# interlock_circuit.net
KiCad netlist of a schematic drawn in Altium Designer
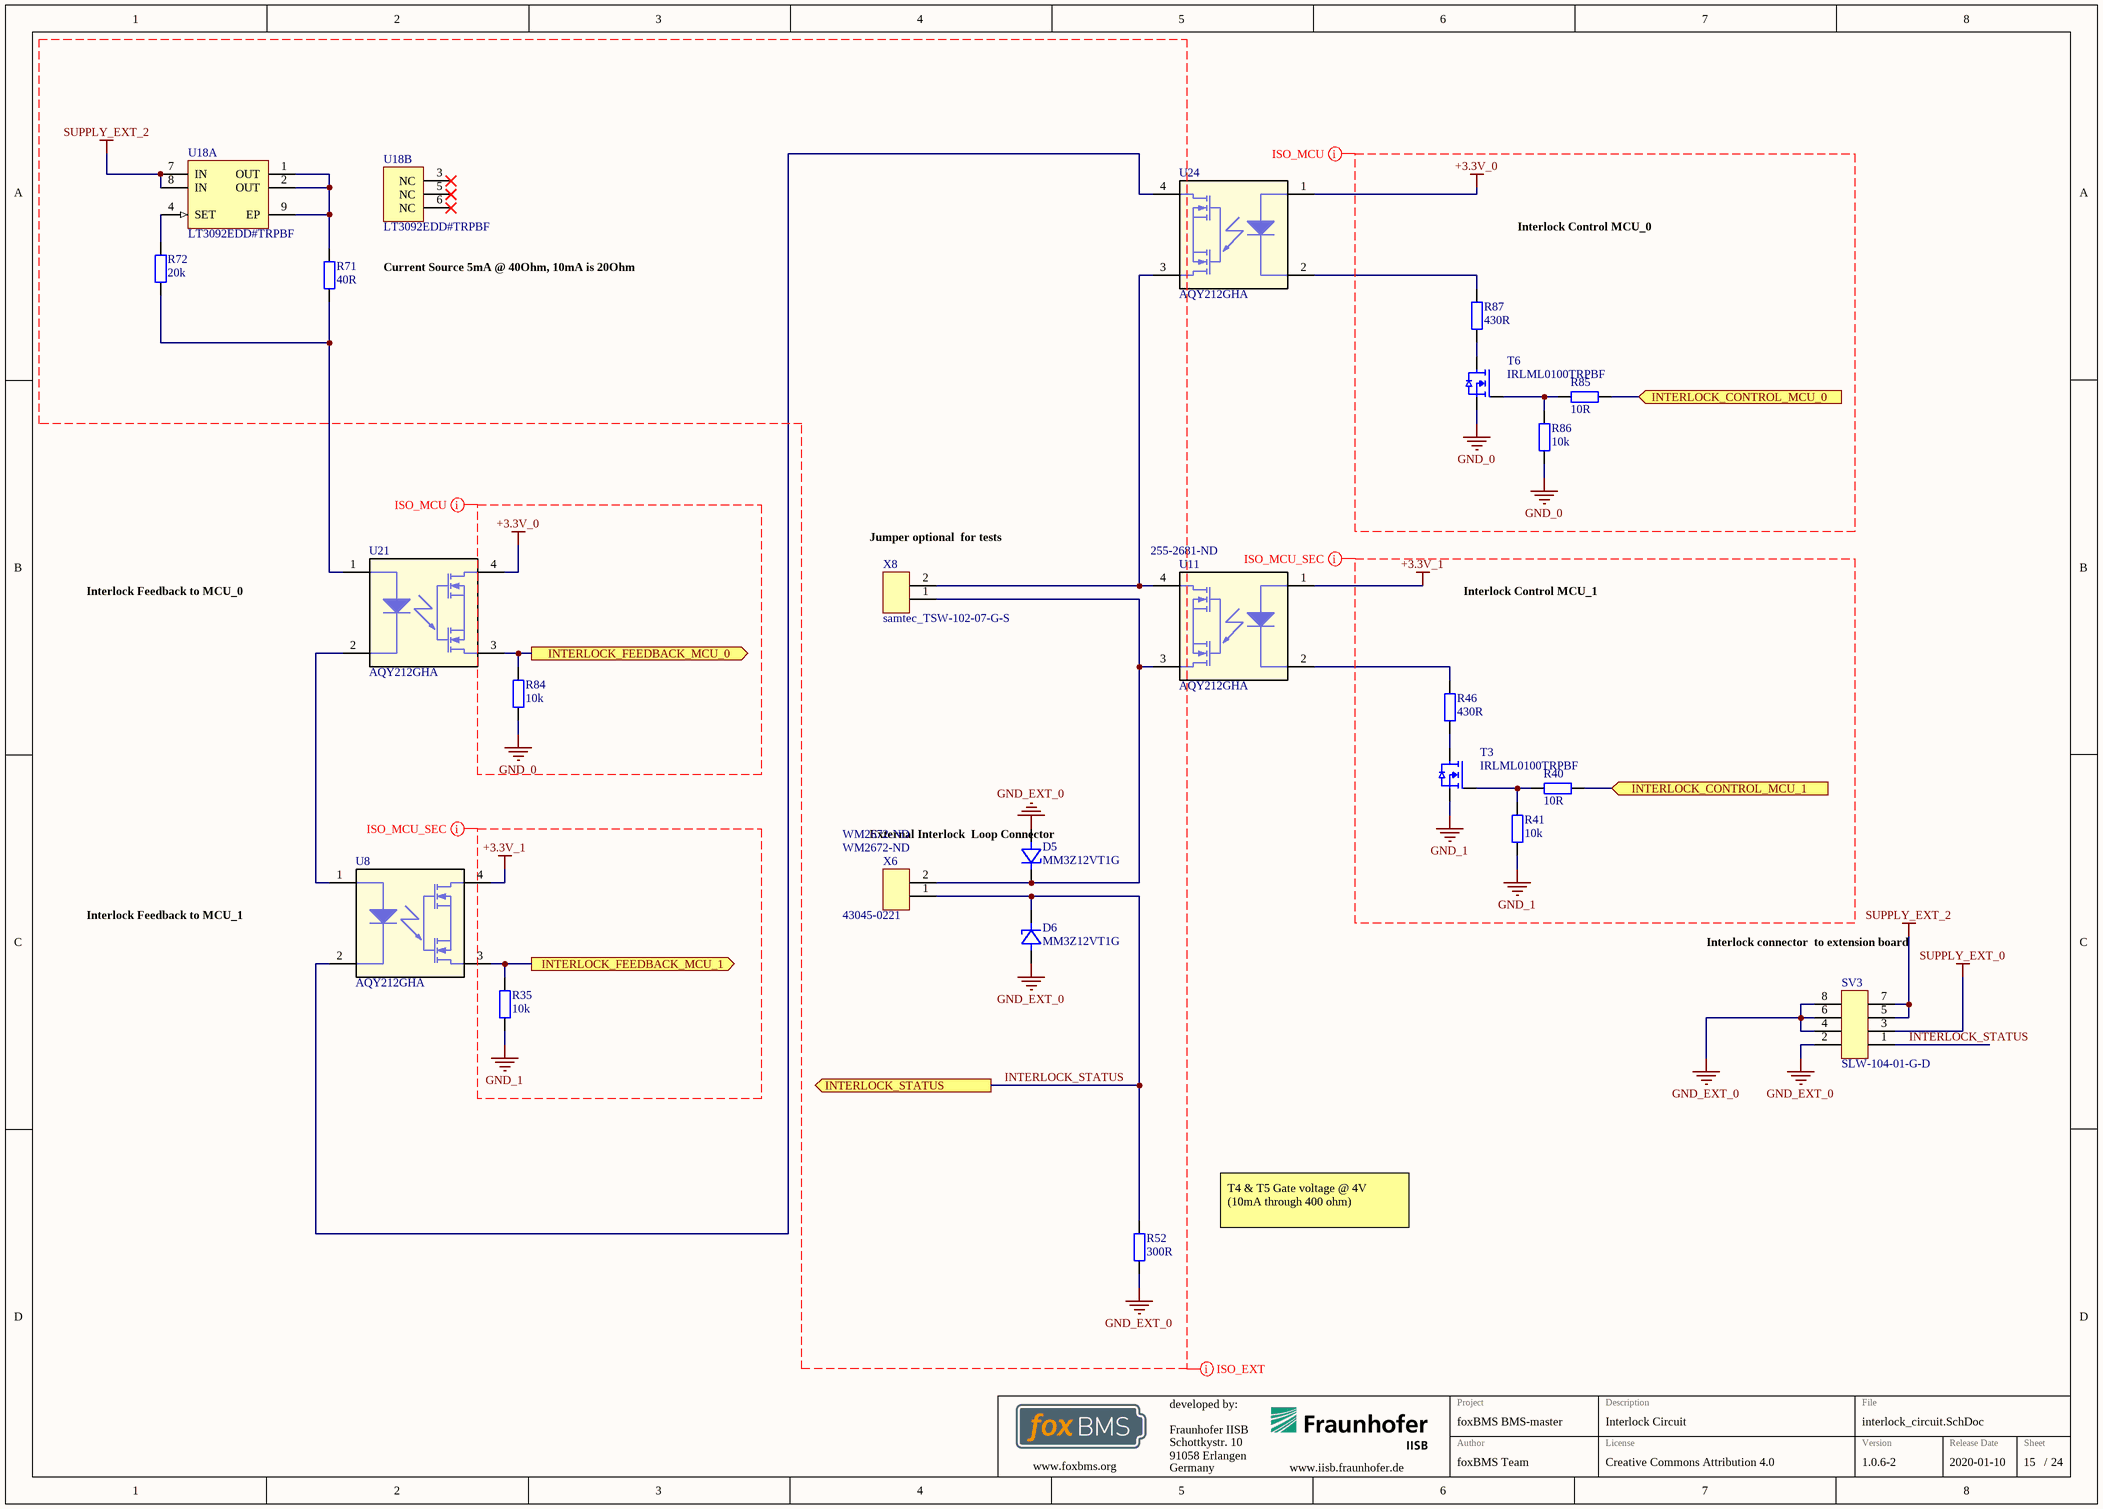
[diagram p0: interlock_circuit.SchDoc]

(export (version "E")
  (design (tool "Eeschema 10.0.6"))
  (components
    (comp (ref "D5")
      (value "MM3Z12VT1G")
      (footprint "SODFL250X110-2N")
      (description "Zener Diode")
      (fields (field (name "MANUFACTURER") "ON Semiconductor"))
      (libsource (lib "OE750") (part "D_Zener"))
    )
    (comp (ref "D6")
      (value "MM3Z12VT1G")
      (footprint "SODFL250X110-2N")
      (description "Zener Diode")
      (fields (field (name "MANUFACTURER") "ON Semiconductor"))
      (libsource (lib "OE750") (part "D_Zener"))
    )
    (comp (ref "R35")
      (value "10k")
      (footprint "0603R")
      (description "SMD Resistor 10k 0603")
      (fields (field (name "PART NUMBER") "gen_R_10k_0603") (field (name "TOLERANCE") "1%"))
      (libsource (lib "master-010106") (part "R"))
    )
    (comp (ref "R40")
      (value "10R")
      (footprint "0603R")
      (description "SMD Resistor 10R 0603")
      (fields (field (name "PART NUMBER") "gen_R_10R_0603") (field (name "TOLERANCE") "1%"))
      (libsource (lib "master-010106") (part "R"))
    )
    (comp (ref "R41")
      (value "10k")
      (footprint "0603R")
      (description "SMD Resistor 10k 0603")
      (fields (field (name "PART NUMBER") "gen_R_10k_0603") (field (name "TOLERANCE") "1%"))
      (libsource (lib "master-010106") (part "R"))
    )
    (comp (ref "R46")
      (value "430R")
      (footprint "0603R")
      (description "SMD Resistor 430R 0603")
      (fields (field (name "PART NUMBER") "gen_R_430R_0603") (field (name "TOLERANCE") "1%"))
      (libsource (lib "master-010106") (part "R"))
    )
    (comp (ref "R52")
      (value "300R")
      (footprint "0805R")
      (description "SMD Resistor 330R 0603")
      (fields (field (name "PART NUMBER") "gen_R_300R_0805") (field (name "POWER") "0.1W"))
      (libsource (lib "master-010106") (part "R"))
    )
    (comp (ref "R71")
      (value "40R")
      (footprint "0805R")
      (description "SMD Resistor 120R 0603")
      (fields (field (name "PART NUMBER") "gen_R_120R_0603") (field (name "TOLERANCE") "1%"))
      (libsource (lib "master-010106") (part "R"))
    )
    (comp (ref "R72")
      (value "20k")
      (footprint "0805R")
      (description "SMD Resistor 120R 0603")
      (fields (field (name "PART NUMBER") "gen_R_120R_0603") (field (name "TOLERANCE") "1%"))
      (libsource (lib "master-010106") (part "R"))
    )
    (comp (ref "R84")
      (value "10k")
      (footprint "0603R")
      (description "SMD Resistor 10k 0603")
      (fields (field (name "PART NUMBER") "gen_R_10k_0603") (field (name "TOLERANCE") "1%"))
      (libsource (lib "master-010106") (part "R"))
    )
    (comp (ref "R85")
      (value "10R")
      (footprint "0603R")
      (description "SMD Resistor 10R 0603")
      (fields (field (name "PART NUMBER") "gen_R_10R_0603") (field (name "TOLERANCE") "1%"))
      (libsource (lib "master-010106") (part "R"))
    )
    (comp (ref "R86")
      (value "10k")
      (footprint "0603R")
      (description "SMD Resistor 10k 0603")
      (fields (field (name "PART NUMBER") "gen_R_10k_0603") (field (name "TOLERANCE") "1%"))
      (libsource (lib "master-010106") (part "R"))
    )
    (comp (ref "R87")
      (value "430R")
      (footprint "0603R")
      (description "SMD Resistor 430R 0603")
      (fields (field (name "PART NUMBER") "gen_R_430R_0603") (field (name "TOLERANCE") "1%"))
      (libsource (lib "master-010106") (part "R"))
    )
    (comp (ref "SV3")
      (value "SLW-104-01-G-D")
      (footprint "SLW_104_01_G_D")
      (description "Board-To-Board Connector, Dual, 2.54 mm, 8 Contacts, Receptacle, SLW Series, Through Hole, 2 Rows")
      (fields (field (name "MANUFACTURER") "Samtec"))
      (libsource (lib "OE750") (part "X2x4"))
    )
    (comp (ref "T3")
      (value "IRLML0100TRPBF")
      (footprint "SOT95P237X110-3N")
      (description "MOSFET-Transistor, n-Kanal, 1.6 A, 100 V, 0.178 ohm, 10 V, 2.5 V")
      (fields (field (name "MANUFACTURER") "Infineon"))
      (libsource (lib "OE750") (part "NMOS"))
    )
    (comp (ref "T6")
      (value "IRLML0100TRPBF")
      (footprint "SOT95P237X110-3N")
      (description "MOSFET-Transistor, n-Kanal, 1.6 A, 100 V, 0.178 ohm, 10 V, 2.5 V")
      (fields (field (name "MANUFACTURER") "Infineon"))
      (libsource (lib "OE750") (part "NMOS"))
    )
    (comp (ref "U8")
      (value "AQY212GHA")
      (footprint "PAN_AQY21-SO4")
      (fields (field (name "MANUFACTURER") "Panasonic"))
      (libsource (lib "master-010106") (part "AQY212GHA"))
    )
    (comp (ref "U11")
      (value "AQY212GHA")
      (footprint "PAN_AQY21-SO4")
      (fields (field (name "MANUFACTURER") "Panasonic") (field (name "SUPPLIER PART NUMBER 1") "255-2681-ND"))
      (libsource (lib "") (part "AQY212GHA_1"))
    )
    (comp (ref "U18")
      (value "LT3092EDD#TRPBF")
      (footprint "LT-DD-8_V")
      (fields (field (name "MANUFACTURER") "Linear Technology"))
      (libsource (lib "Altium Content Vault") (part "LT-LT3092-DD-8"))
    )
    (comp (ref "U21")
      (value "AQY212GHA")
      (footprint "PAN_AQY21-SO4")
      (fields (field (name "MANUFACTURER") "Panasonic"))
      (libsource (lib "master-010106") (part "AQY212GHA"))
    )
    (comp (ref "U24")
      (value "AQY212GHA")
      (footprint "PAN_AQY21-SO4")
      (fields (field (name "MANUFACTURER") "Panasonic"))
      (libsource (lib "") (part "AQY212GHA_1"))
    )
    (comp (ref "X6")
      (value "43045-0221")
      (footprint "43045-0221")
      (fields
        (field (name "PART NUMBER") "molex_microfit_3_01x2_THT")
        (field (name "MANUFACTURER") "Molex")
        (field (name "SUPPLIER PART NUMBER 1") "WM2672-ND")
        (field (name "SUPPLIER PART NUMBER 2") "WM2672-ND")
      )
      (libsource (lib "master-010106") (part "X2"))
    )
    (comp (ref "X8")
      (value "samtec_TSW-102-07-G-S")
      (footprint "Pinheader_2.54_2")
      (description "Board-To-Board Connector, Vertical, 2.54 mm, 2 Contacts, Header, TSW Series, Through Hole, 1 Row")
      (fields (field (name "MANUFACTURER") "Samtec"))
      (libsource (lib "OE750") (part "X2"))
    )
  )
  (nets
    (net (code "1") (name "+3.3V_0") (class "Default")
      (node (ref "U21") (pin "4") (pinfunction "4_4") (pintype "passive"))
      (node (ref "U24") (pin "1") (pinfunction "1_1") (pintype "passive"))
    )
    (net (code "2") (name "+3.3V_1") (class "Default")
      (node (ref "U11") (pin "1") (pinfunction "1_1") (pintype "passive"))
      (node (ref "U8") (pin "4") (pinfunction "4_4") (pintype "passive"))
    )
    (net (code "3") (name "/INTERLOCK_CONTROL_MCU_0") (class "Default")
      (node (ref "R85") (pin "2") (pinfunction "2_2") (pintype "passive"))
    )
    (net (code "4") (name "/INTERLOCK_CONTROL_MCU_1") (class "Default")
      (node (ref "R40") (pin "2") (pinfunction "2_2") (pintype "passive"))
    )
    (net (code "5") (name "/INTERLOCK_FEEDBACK_MCU_0") (class "Default")
      (node (ref "R84") (pin "2") (pinfunction "2_2") (pintype "passive"))
      (node (ref "U21") (pin "3") (pinfunction "3_3") (pintype "passive"))
    )
    (net (code "6") (name "/INTERLOCK_FEEDBACK_MCU_1") (class "Default")
      (node (ref "R35") (pin "2") (pinfunction "2_2") (pintype "passive"))
      (node (ref "U8") (pin "3") (pinfunction "3_3") (pintype "passive"))
    )
    (net (code "7") (name "/INTERLOCK_STATUS") (class "Default")
      (node (ref "D6") (pin "1") (pinfunction "K_1") (pintype "passive"))
      (node (ref "R52") (pin "2") (pinfunction "2_2") (pintype "passive"))
      (node (ref "SV3") (pin "1") (pintype "passive"))
      (node (ref "X6") (pin "1") (pintype "passive"))
    )
    (net (code "8") (name "GND_0") (class "Default")
      (node (ref "R84") (pin "1") (pinfunction "1_1") (pintype "passive"))
      (node (ref "R86") (pin "2") (pinfunction "2_2") (pintype "passive"))
      (node (ref "T6") (pin "S") (pinfunction "S_S") (pintype "passive"))
    )
    (net (code "9") (name "GND_1") (class "Default")
      (node (ref "R35") (pin "1") (pinfunction "1_1") (pintype "passive"))
      (node (ref "R41") (pin "2") (pinfunction "2_2") (pintype "passive"))
      (node (ref "T3") (pin "S") (pinfunction "S_S") (pintype "passive"))
    )
    (net (code "10") (name "GND_EXT_0") (class "Default")
      (node (ref "D5") (pin "2") (pinfunction "A_2") (pintype "passive"))
      (node (ref "D6") (pin "2") (pinfunction "A_2") (pintype "passive"))
      (node (ref "R52") (pin "1") (pinfunction "1_1") (pintype "passive"))
      (node (ref "SV3") (pin "2") (pintype "passive"))
      (node (ref "SV3") (pin "4") (pintype "passive"))
      (node (ref "SV3") (pin "6") (pintype "passive"))
      (node (ref "SV3") (pin "8") (pintype "passive"))
    )
    (net (code "11") (name "Net-(D5-K)") (class "Default")
      (node (ref "D5") (pin "1") (pinfunction "K_1") (pintype "passive"))
      (node (ref "U11") (pin "3") (pinfunction "3_3") (pintype "passive"))
      (node (ref "X6") (pin "2") (pintype "passive"))
      (node (ref "X8") (pin "1") (pintype "passive"))
    )
    (net (code "12") (name "Net-(R40-Pad1)") (class "Default")
      (node (ref "R40") (pin "1") (pinfunction "1_1") (pintype "passive"))
      (node (ref "R41") (pin "1") (pinfunction "1_1") (pintype "passive"))
      (node (ref "T3") (pin "G") (pinfunction "G_G") (pintype "passive"))
    )
    (net (code "13") (name "Net-(R46-Pad1)") (class "Default")
      (node (ref "R46") (pin "1") (pinfunction "1_1") (pintype "passive"))
      (node (ref "T3") (pin "D") (pinfunction "D_D") (pintype "passive"))
    )
    (net (code "14") (name "Net-(R46-Pad2)") (class "Default")
      (node (ref "R46") (pin "2") (pinfunction "2_2") (pintype "passive"))
      (node (ref "U11") (pin "2") (pinfunction "2_2") (pintype "passive"))
    )
    (net (code "15") (name "Net-(R71-Pad1)") (class "Default")
      (node (ref "R71") (pin "1") (pinfunction "1_1") (pintype "passive"))
      (node (ref "R72") (pin "1") (pinfunction "1_1") (pintype "passive"))
      (node (ref "U21") (pin "1") (pinfunction "1_1") (pintype "passive"))
    )
    (net (code "16") (name "Net-(R85-Pad1)") (class "Default")
      (node (ref "R85") (pin "1") (pinfunction "1_1") (pintype "passive"))
      (node (ref "R86") (pin "1") (pinfunction "1_1") (pintype "passive"))
      (node (ref "T6") (pin "G") (pinfunction "G_G") (pintype "passive"))
    )
    (net (code "17") (name "Net-(R87-Pad1)") (class "Default")
      (node (ref "R87") (pin "1") (pinfunction "1_1") (pintype "passive"))
      (node (ref "T6") (pin "D") (pinfunction "D_D") (pintype "passive"))
    )
    (net (code "18") (name "Net-(R87-Pad2)") (class "Default")
      (node (ref "R87") (pin "2") (pinfunction "2_2") (pintype "passive"))
      (node (ref "U24") (pin "2") (pinfunction "2_2") (pintype "passive"))
    )
    (net (code "19") (name "Net-(U11-Pad4)") (class "Default")
      (node (ref "U11") (pin "4") (pinfunction "4_4") (pintype "passive"))
      (node (ref "U24") (pin "3") (pinfunction "3_3") (pintype "passive"))
      (node (ref "X8") (pin "2") (pintype "passive"))
    )
    (net (code "20") (name "Net-(U18A-EP)") (class "Default")
      (node (ref "R71") (pin "2") (pinfunction "2_2") (pintype "passive"))
      (node (ref "U18") (pin "1") (pinfunction "OUT_1") (pintype "power_in"))
      (node (ref "U18") (pin "2") (pinfunction "OUT_2") (pintype "power_in"))
      (node (ref "U18") (pin "9") (pinfunction "EP_9") (pintype "power_in"))
    )
    (net (code "21") (name "Net-(U18A-SET)") (class "Default")
      (node (ref "R72") (pin "2") (pinfunction "2_2") (pintype "passive"))
      (node (ref "U18") (pin "4") (pinfunction "SET_4") (pintype "input"))
    )
    (net (code "22") (name "Net-(U21-Pad2)") (class "Default")
      (node (ref "U21") (pin "2") (pinfunction "2_2") (pintype "passive"))
      (node (ref "U8") (pin "1") (pinfunction "1_1") (pintype "passive"))
    )
    (net (code "23") (name "Net-(U24-Pad4)") (class "Default")
      (node (ref "U24") (pin "4") (pinfunction "4_4") (pintype "passive"))
      (node (ref "U8") (pin "2") (pinfunction "2_2") (pintype "passive"))
    )
    (net (code "24") (name "SUPPLY_EXT_0") (class "Default") (node (ref "SV3") (pin "3") (pintype "passive")))
    (net (code "25") (name "SUPPLY_EXT_2") (class "Default")
      (node (ref "SV3") (pin "5") (pintype "passive"))
      (node (ref "SV3") (pin "7") (pintype "passive"))
      (node (ref "U18") (pin "7") (pinfunction "IN_7") (pintype "power_in"))
      (node (ref "U18") (pin "8") (pinfunction "IN_8") (pintype "power_in"))
    )
    (net (code "26") (name "unconnected-(U18B-NC-Pad3)") (class "Default")
      (node (ref "U18") (pin "3") (pinfunction "NC_3") (pintype "passive+no_connect"))
    )
    (net (code "27") (name "unconnected-(U18B-NC-Pad5)") (class "Default")
      (node (ref "U18") (pin "5") (pinfunction "NC_5") (pintype "passive+no_connect"))
    )
    (net (code "28") (name "unconnected-(U18B-NC-Pad6)") (class "Default")
      (node (ref "U18") (pin "6") (pinfunction "NC_6") (pintype "passive+no_connect"))
    )
  )
)
